# Driver.net
KiCad netlist of a schematic drawn in Altium Designer
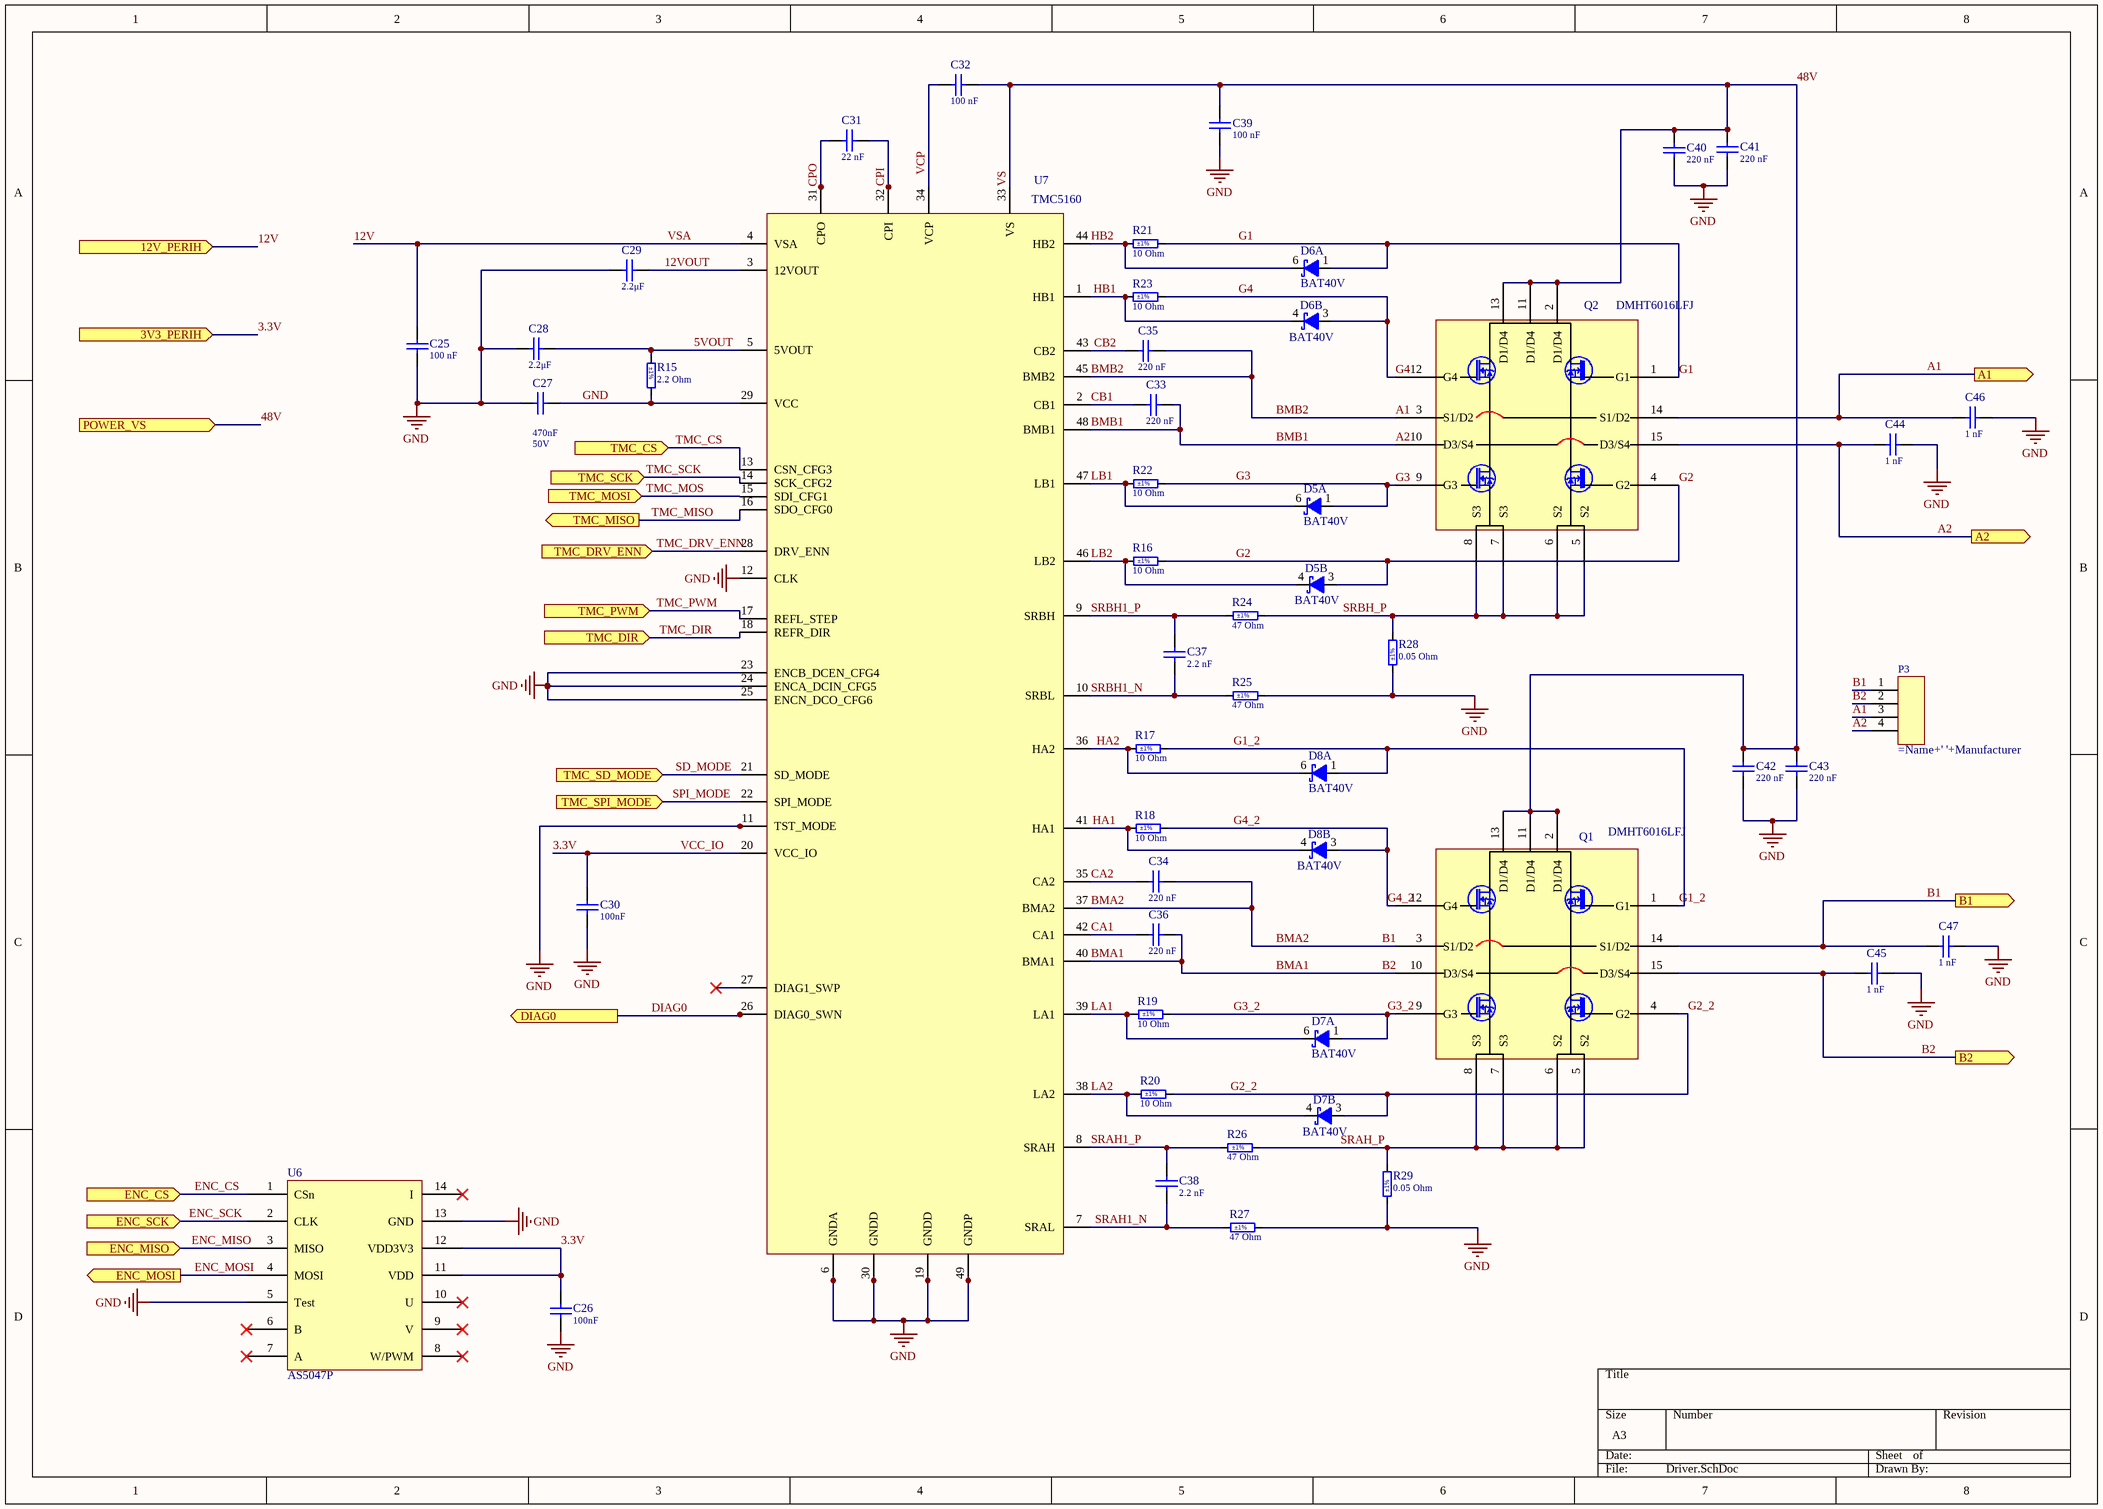
[diagram p0: Driver.SchDoc]

(export (version "E")
  (design (tool "Eeschema 10.0.6"))
  (components
    (comp (ref "C25")
      (value "100 nF 100V X5R ±10%")
      (footprint "capasitors:0402")
      (description "Ceramic capacitor")
      (fields
        (field (name "VOLTAGE") "100V")
        (field (name "TOLERANCE") "±10%")
        (field (name "CAPACITANCE") "100 nF")
      )
      (libsource (lib "passive") (part "Capacitor ceramic"))
    )
    (comp (ref "C26")
      (value "100nF 16V X7R ±10%")
      (footprint "capasitors:0402")
      (description "Ceramic capacitor")
      (fields
        (field (name "VOLTAGE") "16V")
        (field (name "TOLERANCE") "±10%")
        (field (name "CAPACITANCE") "100nF")
      )
      (libsource (lib "passive") (part "Capacitor ceramic"))
    )
    (comp (ref "C27")
      (value "470nF 50V ±10%")
      (footprint "0402")
      (description "Capacitor")
      (fields
        (field (name "TOLERANCE") "±10%")
        (field (name "CAPACITANCE") "470nF")
        (field (name "VOLTAGE") "50V")
        (field (name "MANUFACTURER") "Walsin")
      )
      (libsource (lib "Integrated_Library_Rassipuha_ZEN") (part "Cap"))
    )
    (comp (ref "C28")
      (value "2.2μF 16V X5R 20%")
      (footprint "capasitors:0402")
      (description "Ceramic capacitor")
      (fields
        (field (name "VOLTAGE") "16V")
        (field (name "TOLERANCE") "20%")
        (field (name "CAPACITANCE") "2.2μF")
      )
      (libsource (lib "passive") (part "Capacitor ceramic"))
    )
    (comp (ref "C29")
      (value "2.2μF 16V X5R 20%")
      (footprint "capasitors:0402")
      (description "Ceramic capacitor")
      (fields
        (field (name "VOLTAGE") "16V")
        (field (name "TOLERANCE") "20%")
        (field (name "CAPACITANCE") "2.2μF")
      )
      (libsource (lib "passive") (part "Capacitor ceramic"))
    )
    (comp (ref "C30")
      (value "100nF 16V X7R ±10%")
      (footprint "capasitors:0402")
      (description "Ceramic capacitor")
      (fields
        (field (name "VOLTAGE") "16V")
        (field (name "TOLERANCE") "±10%")
        (field (name "CAPACITANCE") "100nF")
      )
      (libsource (lib "passive") (part "Capacitor ceramic"))
    )
    (comp (ref "C31")
      (value "22 nF 100V X7R ±10%")
      (footprint "capasitors:0603")
      (description "Ceramic capacitor")
      (fields
        (field (name "VOLTAGE") "100V")
        (field (name "TOLERANCE") "±10%")
        (field (name "CAPACITANCE") "22 nF")
      )
      (libsource (lib "passive") (part "Capacitor ceramic"))
    )
    (comp (ref "C32")
      (value "100 nF 100V X5R ±10%")
      (footprint "capasitors:0402")
      (description "Ceramic capacitor")
      (fields
        (field (name "VOLTAGE") "100V")
        (field (name "TOLERANCE") "±10%")
        (field (name "CAPACITANCE") "100 nF")
      )
      (libsource (lib "passive") (part "Capacitor ceramic"))
    )
    (comp (ref "C33")
      (value "220 nF 25 X7R ±10%")
      (footprint "capasitors:0402")
      (description "Ceramic capacitor")
      (fields
        (field (name "VOLTAGE") "25")
        (field (name "TOLERANCE") "±10%")
        (field (name "CAPACITANCE") "220 nF")
      )
      (libsource (lib "passive") (part "Capacitor ceramic"))
    )
    (comp (ref "C34")
      (value "220 nF 25 X7R ±10%")
      (footprint "capasitors:0402")
      (description "Ceramic capacitor")
      (fields
        (field (name "VOLTAGE") "25")
        (field (name "TOLERANCE") "±10%")
        (field (name "CAPACITANCE") "220 nF")
      )
      (libsource (lib "passive") (part "Capacitor ceramic"))
    )
    (comp (ref "C35")
      (value "220 nF 25 X7R ±10%")
      (footprint "capasitors:0603")
      (description "Ceramic capacitor")
      (fields
        (field (name "VOLTAGE") "25")
        (field (name "TOLERANCE") "±10%")
        (field (name "CAPACITANCE") "220 nF")
      )
      (libsource (lib "passive") (part "Capacitor ceramic"))
    )
    (comp (ref "C36")
      (value "220 nF 25 X7R ±10%")
      (footprint "capasitors:0603")
      (description "Ceramic capacitor")
      (fields
        (field (name "VOLTAGE") "25")
        (field (name "TOLERANCE") "±10%")
        (field (name "CAPACITANCE") "220 nF")
      )
      (libsource (lib "passive") (part "Capacitor ceramic"))
    )
    (comp (ref "C37")
      (value "2.2 nF 100V X7R ±10%")
      (footprint "capasitors:0402")
      (description "Ceramic capacitor")
      (fields
        (field (name "VOLTAGE") "100V")
        (field (name "TOLERANCE") "±10%")
        (field (name "CAPACITANCE") "2.2 nF")
      )
      (libsource (lib "passive") (part "Capacitor ceramic"))
    )
    (comp (ref "C38")
      (value "2.2 nF 100V X7R ±10%")
      (footprint "capasitors:0402")
      (description "Ceramic capacitor")
      (fields
        (field (name "VOLTAGE") "100V")
        (field (name "TOLERANCE") "±10%")
        (field (name "CAPACITANCE") "2.2 nF")
      )
      (libsource (lib "passive") (part "Capacitor ceramic"))
    )
    (comp (ref "C39")
      (value "100 nF 100V X5R ±10%")
      (footprint "capasitors:0402")
      (description "Ceramic capacitor")
      (fields
        (field (name "VOLTAGE") "100V")
        (field (name "TOLERANCE") "±10%")
        (field (name "CAPACITANCE") "100 nF")
      )
      (libsource (lib "passive") (part "Capacitor ceramic"))
    )
    (comp (ref "C40")
      (value "220 nF 100V X7S ±10%")
      (footprint "capasitors:0603")
      (description "Ceramic capacitor")
      (fields
        (field (name "VOLTAGE") "100V")
        (field (name "TOLERANCE") "±10%")
        (field (name "CAPACITANCE") "220 nF")
      )
      (libsource (lib "passive") (part "Capacitor ceramic"))
    )
    (comp (ref "C41")
      (value "220 nF 100V X7S ±10%")
      (footprint "capasitors:0603")
      (description "Ceramic capacitor")
      (fields
        (field (name "VOLTAGE") "100V")
        (field (name "TOLERANCE") "±10%")
        (field (name "CAPACITANCE") "220 nF")
      )
      (libsource (lib "passive") (part "Capacitor ceramic"))
    )
    (comp (ref "C42")
      (value "220 nF 100V X7S ±10%")
      (footprint "capasitors:0603")
      (description "Ceramic capacitor")
      (fields
        (field (name "VOLTAGE") "100V")
        (field (name "TOLERANCE") "±10%")
        (field (name "CAPACITANCE") "220 nF")
      )
      (libsource (lib "passive") (part "Capacitor ceramic"))
    )
    (comp (ref "C43")
      (value "220 nF 100V X7S ±10%")
      (footprint "capasitors:0603")
      (description "Ceramic capacitor")
      (fields
        (field (name "VOLTAGE") "100V")
        (field (name "TOLERANCE") "±10%")
        (field (name "CAPACITANCE") "220 nF")
      )
      (libsource (lib "passive") (part "Capacitor ceramic"))
    )
    (comp (ref "C44")
      (value "1 nF 100V X7R ±10%")
      (footprint "capasitors:0402")
      (description "Ceramic capacitor")
      (fields
        (field (name "VOLTAGE") "100V")
        (field (name "TOLERANCE") "±10%")
        (field (name "CAPACITANCE") "1 nF")
      )
      (libsource (lib "passive") (part "Capacitor ceramic"))
    )
    (comp (ref "C45")
      (value "1 nF 100V X7R ±10%")
      (footprint "capasitors:0402")
      (description "Ceramic capacitor")
      (fields
        (field (name "VOLTAGE") "100V")
        (field (name "TOLERANCE") "±10%")
        (field (name "CAPACITANCE") "1 nF")
      )
      (libsource (lib "passive") (part "Capacitor ceramic"))
    )
    (comp (ref "C46")
      (value "1 nF 100V X7R ±10%")
      (footprint "capasitors:0402")
      (description "Ceramic capacitor")
      (fields
        (field (name "VOLTAGE") "100V")
        (field (name "TOLERANCE") "±10%")
        (field (name "CAPACITANCE") "1 nF")
      )
      (libsource (lib "passive") (part "Capacitor ceramic"))
    )
    (comp (ref "C47")
      (value "1 nF 100V X7R ±10%")
      (footprint "capasitors:0402")
      (description "Ceramic capacitor")
      (fields
        (field (name "VOLTAGE") "100V")
        (field (name "TOLERANCE") "±10%")
        (field (name "CAPACITANCE") "1 nF")
      )
      (libsource (lib "passive") (part "Capacitor ceramic"))
    )
    (comp (ref "D5") (value "BAT40V") (footprint "SOT563-6") (libsource (lib "") (part "BAT40V_1")))
    (comp (ref "D6") (value "BAT40V") (footprint "SOT563-6") (libsource (lib "") (part "BAT40V_1")))
    (comp (ref "D7")
      (value "BAT40V")
      (footprint "SOT563-6")
      (libsource (lib "Integrated_Library_Rassipuha_ZEN") (part "BAT40V"))
    )
    (comp (ref "D8")
      (value "BAT40V")
      (footprint "SOT563-6")
      (libsource (lib "Integrated_Library_Rassipuha_ZEN") (part "BAT40V"))
    )
    (comp (ref "P3")
      (value "Dinkle")
      (footprint "CONN_TERMBLOCK:15EDGRC-3.5-04P")
      (fields (field (name "MANUFACTURER") "Dinkle"))
      (libsource (lib "connector") (part "TerminalBlock4"))
    )
    (comp (ref "Q1")
      (value "DMHT6016LFJ")
      (footprint "V-DFN5045-12 (Type B)")
      (libsource (lib "Integrated_Library_Rassipuha_ZEN") (part "DMHT6016LFJ"))
    )
    (comp (ref "Q2")
      (value "DMHT6016LFJ")
      (footprint "V-DFN5045-12 (Type B)")
      (libsource (lib "Integrated_Library_Rassipuha_ZEN") (part "DMHT6016LFJ"))
    )
    (comp (ref "R15")
      (value "2.2 Ohm 1/10 W")
      (footprint "resistor:0603")
      (description "Thik Film Chip Resistor")
      (fields
        (field (name "POWER") "1/10 W")
        (field (name "TOLERANCE") "±1%")
        (field (name "RESISTANCE") "2.2 Ohm")
      )
      (libsource (lib "passive") (part "Resistor"))
    )
    (comp (ref "R16")
      (value "10 Ohm 1/16 W")
      (footprint "resistor:0402")
      (description "Thik Film Chip Resistor")
      (fields
        (field (name "POWER") "1/16 W")
        (field (name "TOLERANCE") "±1%")
        (field (name "RESISTANCE") "10 Ohm")
      )
      (libsource (lib "passive") (part "Resistor"))
    )
    (comp (ref "R17")
      (value "10 Ohm 1/16 W")
      (footprint "resistor:0402")
      (description "Thik Film Chip Resistor")
      (fields
        (field (name "POWER") "1/16 W")
        (field (name "TOLERANCE") "±1%")
        (field (name "RESISTANCE") "10 Ohm")
      )
      (libsource (lib "passive") (part "Resistor"))
    )
    (comp (ref "R18")
      (value "10 Ohm 1/16 W")
      (footprint "resistor:0402")
      (description "Thik Film Chip Resistor")
      (fields
        (field (name "POWER") "1/16 W")
        (field (name "TOLERANCE") "±1%")
        (field (name "RESISTANCE") "10 Ohm")
      )
      (libsource (lib "passive") (part "Resistor"))
    )
    (comp (ref "R19")
      (value "10 Ohm 1/16 W")
      (footprint "resistor:0402")
      (description "Thik Film Chip Resistor")
      (fields
        (field (name "POWER") "1/16 W")
        (field (name "TOLERANCE") "±1%")
        (field (name "RESISTANCE") "10 Ohm")
      )
      (libsource (lib "passive") (part "Resistor"))
    )
    (comp (ref "R20")
      (value "10 Ohm 1/16 W")
      (footprint "resistor:0402")
      (description "Thik Film Chip Resistor")
      (fields
        (field (name "POWER") "1/16 W")
        (field (name "TOLERANCE") "±1%")
        (field (name "RESISTANCE") "10 Ohm")
      )
      (libsource (lib "passive") (part "Resistor"))
    )
    (comp (ref "R21")
      (value "10 Ohm 1/16 W")
      (footprint "resistor:0402")
      (description "Thik Film Chip Resistor")
      (fields
        (field (name "POWER") "1/16 W")
        (field (name "TOLERANCE") "±1%")
        (field (name "RESISTANCE") "10 Ohm")
      )
      (libsource (lib "passive") (part "Resistor"))
    )
    (comp (ref "R22")
      (value "10 Ohm 1/16 W")
      (footprint "resistor:0402")
      (description "Thik Film Chip Resistor")
      (fields
        (field (name "POWER") "1/16 W")
        (field (name "TOLERANCE") "±1%")
        (field (name "RESISTANCE") "10 Ohm")
      )
      (libsource (lib "passive") (part "Resistor"))
    )
    (comp (ref "R23")
      (value "10 Ohm 1/16 W")
      (footprint "resistor:0402")
      (description "Thik Film Chip Resistor")
      (fields
        (field (name "POWER") "1/16 W")
        (field (name "TOLERANCE") "±1%")
        (field (name "RESISTANCE") "10 Ohm")
      )
      (libsource (lib "passive") (part "Resistor"))
    )
    (comp (ref "R24")
      (value "47 Ohm 1/16 W")
      (footprint "resistor:0402")
      (description "Thik Film Chip Resistor")
      (fields
        (field (name "POWER") "1/16 W")
        (field (name "TOLERANCE") "±1%")
        (field (name "RESISTANCE") "47 Ohm")
      )
      (libsource (lib "passive") (part "Resistor"))
    )
    (comp (ref "R25")
      (value "47 Ohm 1/16 W")
      (footprint "resistor:0402")
      (description "Thik Film Chip Resistor")
      (fields
        (field (name "POWER") "1/16 W")
        (field (name "TOLERANCE") "±1%")
        (field (name "RESISTANCE") "47 Ohm")
      )
      (libsource (lib "passive") (part "Resistor"))
    )
    (comp (ref "R26")
      (value "47 Ohm 1/16 W")
      (footprint "resistor:0402")
      (description "Thik Film Chip Resistor")
      (fields
        (field (name "POWER") "1/16 W")
        (field (name "TOLERANCE") "±1%")
        (field (name "RESISTANCE") "47 Ohm")
      )
      (libsource (lib "passive") (part "Resistor"))
    )
    (comp (ref "R27")
      (value "47 Ohm 1/16 W")
      (footprint "resistor:0402")
      (description "Thik Film Chip Resistor")
      (fields
        (field (name "POWER") "1/16 W")
        (field (name "TOLERANCE") "±1%")
        (field (name "RESISTANCE") "47 Ohm")
      )
      (libsource (lib "passive") (part "Resistor"))
    )
    (comp (ref "R28")
      (value "0.05 Ohm 1 W")
      (footprint "resistor:1206")
      (description "Thik Film Chip Resistor")
      (fields
        (field (name "POWER") "1 W")
        (field (name "TOLERANCE") "±1%")
        (field (name "RESISTANCE") "0.05 Ohm")
      )
      (libsource (lib "passive") (part "Resistor"))
    )
    (comp (ref "R29")
      (value "0.05 Ohm 1 W")
      (footprint "resistor:1206")
      (description "Thik Film Chip Resistor")
      (fields
        (field (name "POWER") "1 W")
        (field (name "TOLERANCE") "±1%")
        (field (name "RESISTANCE") "0.05 Ohm")
      )
      (libsource (lib "passive") (part "Resistor"))
    )
    (comp (ref "U6")
      (value "AS5047P")
      (footprint "TSSOP-14-0.65")
      (libsource (lib "Integrated_Library_IC_ZEN") (part "AS5047P"))
    )
    (comp (ref "U7")
      (value "TMC5160")
      (footprint "TQFP48-0.5-EP")
      (libsource (lib "ic_driver") (part "TMC5160"))
    )
  )
  (nets
    (net (code "1") (name "/3.3V") (class "Default")
      (node (ref "C26") (pin "2") (pinfunction "2_2") (pintype "passive"))
      (node (ref "C30") (pin "2") (pinfunction "2_2") (pintype "passive"))
      (node (ref "U6") (pin "11") (pinfunction "VDD_11") (pintype "passive"))
      (node (ref "U6") (pin "12") (pinfunction "VDD3V3_12") (pintype "passive"))
      (node (ref "U7") (pin "20") (pinfunction "VCC_IO_20") (pintype "passive"))
    )
    (net (code "2") (name "/5VOUT") (class "Default")
      (node (ref "C28") (pin "2") (pinfunction "2_2") (pintype "passive"))
      (node (ref "R15") (pin "1") (pinfunction "1_1") (pintype "passive"))
      (node (ref "U7") (pin "5") (pinfunction "5VOUT_5") (pintype "passive"))
    )
    (net (code "3") (name "/12V") (class "Default")
      (node (ref "C25") (pin "1") (pinfunction "1_1") (pintype "passive"))
      (node (ref "U7") (pin "4") (pinfunction "VSA_4") (pintype "passive"))
    )
    (net (code "4") (name "/12VOUT") (class "Default")
      (node (ref "C29") (pin "2") (pinfunction "2_2") (pintype "passive"))
      (node (ref "U7") (pin "3") (pinfunction "12VOUT_3") (pintype "passive"))
    )
    (net (code "5") (name "/48V") (class "Default")
      (node (ref "C32") (pin "2") (pinfunction "2_2") (pintype "passive"))
      (node (ref "C39") (pin "1") (pinfunction "1_1") (pintype "passive"))
      (node (ref "C40") (pin "1") (pinfunction "1_1") (pintype "passive"))
      (node (ref "C41") (pin "2") (pinfunction "2_2") (pintype "passive"))
      (node (ref "C42") (pin "2") (pinfunction "2_2") (pintype "passive"))
      (node (ref "C43") (pin "2") (pinfunction "2_2") (pintype "passive"))
      (node (ref "Q1") (pin "11") (pinfunction "D1/D4_11") (pintype "passive"))
      (node (ref "Q1") (pin "13") (pinfunction "D1/D4_13") (pintype "passive"))
      (node (ref "Q1") (pin "2") (pinfunction "D1/D4_2") (pintype "passive"))
      (node (ref "Q2") (pin "11") (pinfunction "D1/D4_11") (pintype "passive"))
      (node (ref "Q2") (pin "13") (pinfunction "D1/D4_13") (pintype "passive"))
      (node (ref "Q2") (pin "2") (pinfunction "D1/D4_2") (pintype "passive"))
      (node (ref "U7") (pin "33") (pinfunction "VS_33") (pintype "passive"))
    )
    (net (code "6") (name "/A1") (class "Default")
      (node (ref "C35") (pin "2") (pinfunction "2_2") (pintype "passive"))
      (node (ref "C46") (pin "2") (pinfunction "2_2") (pintype "passive"))
      (node (ref "P3") (pin "3") (pinfunction "3_3") (pintype "passive"))
      (node (ref "Q2") (pin "14") (pinfunction "S1/D2_14") (pintype "passive"))
      (node (ref "Q2") (pin "3") (pinfunction "S1/D2_3") (pintype "passive"))
      (node (ref "U7") (pin "45") (pinfunction "BMB2_45") (pintype "passive"))
    )
    (net (code "7") (name "/A2") (class "Default")
      (node (ref "C33") (pin "2") (pinfunction "2_2") (pintype "passive"))
      (node (ref "C44") (pin "2") (pinfunction "2_2") (pintype "passive"))
      (node (ref "P3") (pin "4") (pinfunction "4_4") (pintype "passive"))
      (node (ref "Q2") (pin "10") (pinfunction "D3/S4_10") (pintype "passive"))
      (node (ref "Q2") (pin "15") (pinfunction "D3/S4_15") (pintype "passive"))
      (node (ref "U7") (pin "48") (pinfunction "BMB1_48") (pintype "passive"))
    )
    (net (code "8") (name "/B1") (class "Default")
      (node (ref "C34") (pin "2") (pinfunction "2_2") (pintype "passive"))
      (node (ref "C47") (pin "2") (pinfunction "2_2") (pintype "passive"))
      (node (ref "P3") (pin "1") (pinfunction "1_1") (pintype "passive"))
      (node (ref "Q1") (pin "14") (pinfunction "S1/D2_14") (pintype "passive"))
      (node (ref "Q1") (pin "3") (pinfunction "S1/D2_3") (pintype "passive"))
      (node (ref "U7") (pin "37") (pinfunction "BMA2_37") (pintype "passive"))
    )
    (net (code "9") (name "/B2") (class "Default")
      (node (ref "C36") (pin "2") (pinfunction "2_2") (pintype "passive"))
      (node (ref "C45") (pin "2") (pinfunction "2_2") (pintype "passive"))
      (node (ref "P3") (pin "2") (pinfunction "2_2") (pintype "passive"))
      (node (ref "Q1") (pin "10") (pinfunction "D3/S4_10") (pintype "passive"))
      (node (ref "Q1") (pin "15") (pinfunction "D3/S4_15") (pintype "passive"))
      (node (ref "U7") (pin "40") (pinfunction "BMA1_40") (pintype "passive"))
    )
    (net (code "10") (name "/CA1") (class "Default")
      (node (ref "C36") (pin "1") (pinfunction "1_1") (pintype "passive"))
      (node (ref "U7") (pin "42") (pinfunction "CA1_42") (pintype "passive"))
    )
    (net (code "11") (name "/CA2") (class "Default")
      (node (ref "C34") (pin "1") (pinfunction "1_1") (pintype "passive"))
      (node (ref "U7") (pin "35") (pinfunction "CA2_35") (pintype "passive"))
    )
    (net (code "12") (name "/CB1") (class "Default")
      (node (ref "C33") (pin "1") (pinfunction "1_1") (pintype "passive"))
      (node (ref "U7") (pin "2") (pinfunction "CB1_2") (pintype "passive"))
    )
    (net (code "13") (name "/CB2") (class "Default")
      (node (ref "C35") (pin "1") (pinfunction "1_1") (pintype "passive"))
      (node (ref "U7") (pin "43") (pinfunction "CB2_43") (pintype "passive"))
    )
    (net (code "14") (name "/CPI") (class "Default")
      (node (ref "C31") (pin "2") (pinfunction "2_2") (pintype "passive"))
      (node (ref "U7") (pin "32") (pinfunction "CPI_32") (pintype "passive"))
    )
    (net (code "15") (name "/CPO") (class "Default")
      (node (ref "C31") (pin "1") (pinfunction "1_1") (pintype "passive"))
      (node (ref "U7") (pin "31") (pinfunction "CPO_31") (pintype "passive"))
    )
    (net (code "16") (name "/DIAG0") (class "Default")
      (node (ref "U7") (pin "26") (pinfunction "DIAG0_SWN_26") (pintype "passive"))
    )
    (net (code "17") (name "/ENC_CS") (class "Default")
      (node (ref "U6") (pin "1") (pinfunction "CSn_1") (pintype "passive"))
    )
    (net (code "18") (name "/ENC_MISO") (class "Default")
      (node (ref "U6") (pin "3") (pinfunction "MISO_3") (pintype "passive"))
    )
    (net (code "19") (name "/ENC_MOSI") (class "Default")
      (node (ref "U6") (pin "4") (pinfunction "MOSI_4") (pintype "passive"))
    )
    (net (code "20") (name "/ENC_SCK") (class "Default")
      (node (ref "U6") (pin "2") (pinfunction "CLK_2") (pintype "passive"))
    )
    (net (code "21") (name "/G1") (class "Default")
      (node (ref "D6") (pin "1") (pinfunction "1_1") (pintype "passive"))
      (node (ref "Q2") (pin "1") (pinfunction "G1_1") (pintype "passive"))
      (node (ref "R21") (pin "2") (pinfunction "2_2") (pintype "passive"))
    )
    (net (code "22") (name "/G1_2") (class "Default")
      (node (ref "D8") (pin "1") (pinfunction "1_1") (pintype "passive"))
      (node (ref "Q1") (pin "1") (pinfunction "G1_1") (pintype "passive"))
      (node (ref "R17") (pin "2") (pinfunction "2_2") (pintype "passive"))
    )
    (net (code "23") (name "/G2") (class "Default")
      (node (ref "D5") (pin "3") (pinfunction "1_3") (pintype "passive"))
      (node (ref "Q2") (pin "4") (pinfunction "G2_4") (pintype "passive"))
      (node (ref "R16") (pin "2") (pinfunction "2_2") (pintype "passive"))
    )
    (net (code "24") (name "/G2_2") (class "Default")
      (node (ref "D7") (pin "3") (pinfunction "1_3") (pintype "passive"))
      (node (ref "Q1") (pin "4") (pinfunction "G2_4") (pintype "passive"))
      (node (ref "R20") (pin "2") (pinfunction "2_2") (pintype "passive"))
    )
    (net (code "25") (name "/G3") (class "Default")
      (node (ref "D5") (pin "1") (pinfunction "1_1") (pintype "passive"))
      (node (ref "Q2") (pin "9") (pinfunction "G3_9") (pintype "passive"))
      (node (ref "R22") (pin "2") (pinfunction "2_2") (pintype "passive"))
    )
    (net (code "26") (name "/G3_2") (class "Default")
      (node (ref "D7") (pin "1") (pinfunction "1_1") (pintype "passive"))
      (node (ref "Q1") (pin "9") (pinfunction "G3_9") (pintype "passive"))
      (node (ref "R19") (pin "2") (pinfunction "2_2") (pintype "passive"))
    )
    (net (code "27") (name "/G4") (class "Default")
      (node (ref "D6") (pin "3") (pinfunction "1_3") (pintype "passive"))
      (node (ref "Q2") (pin "12") (pinfunction "G4_12") (pintype "passive"))
      (node (ref "R23") (pin "2") (pinfunction "2_2") (pintype "passive"))
    )
    (net (code "28") (name "/G4_2") (class "Default")
      (node (ref "D8") (pin "3") (pinfunction "1_3") (pintype "passive"))
      (node (ref "Q1") (pin "12") (pinfunction "G4_12") (pintype "passive"))
      (node (ref "R18") (pin "2") (pinfunction "2_2") (pintype "passive"))
    )
    (net (code "29") (name "/HA1") (class "Default")
      (node (ref "D8") (pin "4") (pinfunction "2_4") (pintype "passive"))
      (node (ref "R18") (pin "1") (pinfunction "1_1") (pintype "passive"))
      (node (ref "U7") (pin "41") (pinfunction "HA1_41") (pintype "passive"))
    )
    (net (code "30") (name "/HA2") (class "Default")
      (node (ref "D8") (pin "6") (pinfunction "2_6") (pintype "passive"))
      (node (ref "R17") (pin "1") (pinfunction "1_1") (pintype "passive"))
      (node (ref "U7") (pin "36") (pinfunction "HA2_36") (pintype "passive"))
    )
    (net (code "31") (name "/HB1") (class "Default")
      (node (ref "D6") (pin "4") (pinfunction "2_4") (pintype "passive"))
      (node (ref "R23") (pin "1") (pinfunction "1_1") (pintype "passive"))
      (node (ref "U7") (pin "1") (pinfunction "HB1_1") (pintype "passive"))
    )
    (net (code "32") (name "/HB2") (class "Default")
      (node (ref "D6") (pin "6") (pinfunction "2_6") (pintype "passive"))
      (node (ref "R21") (pin "1") (pinfunction "1_1") (pintype "passive"))
      (node (ref "U7") (pin "44") (pinfunction "HB2_44") (pintype "passive"))
    )
    (net (code "33") (name "/LA1") (class "Default")
      (node (ref "D7") (pin "6") (pinfunction "2_6") (pintype "passive"))
      (node (ref "R19") (pin "1") (pinfunction "1_1") (pintype "passive"))
      (node (ref "U7") (pin "39") (pinfunction "LA1_39") (pintype "passive"))
    )
    (net (code "34") (name "/LA2") (class "Default")
      (node (ref "D7") (pin "4") (pinfunction "2_4") (pintype "passive"))
      (node (ref "R20") (pin "1") (pinfunction "1_1") (pintype "passive"))
      (node (ref "U7") (pin "38") (pinfunction "LA2_38") (pintype "passive"))
    )
    (net (code "35") (name "/LB1") (class "Default")
      (node (ref "D5") (pin "6") (pinfunction "2_6") (pintype "passive"))
      (node (ref "R22") (pin "1") (pinfunction "1_1") (pintype "passive"))
      (node (ref "U7") (pin "47") (pinfunction "LB1_47") (pintype "passive"))
    )
    (net (code "36") (name "/LB2") (class "Default")
      (node (ref "D5") (pin "4") (pinfunction "2_4") (pintype "passive"))
      (node (ref "R16") (pin "1") (pinfunction "1_1") (pintype "passive"))
      (node (ref "U7") (pin "46") (pinfunction "LB2_46") (pintype "passive"))
    )
    (net (code "37") (name "/SD_MODE") (class "Default")
      (node (ref "U7") (pin "21") (pinfunction "SD_MODE_21") (pintype "passive"))
    )
    (net (code "38") (name "/SPI_MODE") (class "Default")
      (node (ref "U7") (pin "22") (pinfunction "SPI_MODE_22") (pintype "passive"))
    )
    (net (code "39") (name "/SRAH1_N") (class "Default")
      (node (ref "C38") (pin "1") (pinfunction "1_1") (pintype "passive"))
      (node (ref "R27") (pin "1") (pinfunction "1_1") (pintype "passive"))
      (node (ref "U7") (pin "7") (pinfunction "SRAL_7") (pintype "passive"))
    )
    (net (code "40") (name "/SRAH1_P") (class "Default")
      (node (ref "C38") (pin "2") (pinfunction "2_2") (pintype "passive"))
      (node (ref "R26") (pin "1") (pinfunction "1_1") (pintype "passive"))
      (node (ref "U7") (pin "8") (pinfunction "SRAH_8") (pintype "passive"))
    )
    (net (code "41") (name "/SRAH_P") (class "Default")
      (node (ref "Q1") (pin "5") (pinfunction "S2_5") (pintype "passive"))
      (node (ref "Q1") (pin "6") (pinfunction "S2_6") (pintype "passive"))
      (node (ref "Q1") (pin "7") (pinfunction "S3_7") (pintype "passive"))
      (node (ref "Q1") (pin "8") (pinfunction "S3_8") (pintype "passive"))
      (node (ref "R26") (pin "2") (pinfunction "2_2") (pintype "passive"))
      (node (ref "R29") (pin "2") (pinfunction "2_2") (pintype "passive"))
    )
    (net (code "42") (name "/SRBH1_N") (class "Default")
      (node (ref "C37") (pin "1") (pinfunction "1_1") (pintype "passive"))
      (node (ref "R25") (pin "1") (pinfunction "1_1") (pintype "passive"))
      (node (ref "U7") (pin "10") (pinfunction "SRBL_10") (pintype "passive"))
    )
    (net (code "43") (name "/SRBH1_P") (class "Default")
      (node (ref "C37") (pin "2") (pinfunction "2_2") (pintype "passive"))
      (node (ref "R24") (pin "1") (pinfunction "1_1") (pintype "passive"))
      (node (ref "U7") (pin "9") (pinfunction "SRBH_9") (pintype "passive"))
    )
    (net (code "44") (name "/SRBH_P") (class "Default")
      (node (ref "Q2") (pin "5") (pinfunction "S2_5") (pintype "passive"))
      (node (ref "Q2") (pin "6") (pinfunction "S2_6") (pintype "passive"))
      (node (ref "Q2") (pin "7") (pinfunction "S3_7") (pintype "passive"))
      (node (ref "Q2") (pin "8") (pinfunction "S3_8") (pintype "passive"))
      (node (ref "R24") (pin "2") (pinfunction "2_2") (pintype "passive"))
      (node (ref "R28") (pin "2") (pinfunction "2_2") (pintype "passive"))
    )
    (net (code "45") (name "/TMC_CS") (class "Default")
      (node (ref "U7") (pin "13") (pinfunction "CSN_CFG3_13") (pintype "passive"))
    )
    (net (code "46") (name "/TMC_DIR") (class "Default")
      (node (ref "U7") (pin "18") (pinfunction "REFR_DIR_18") (pintype "passive"))
    )
    (net (code "47") (name "/TMC_DRV_ENN") (class "Default")
      (node (ref "U7") (pin "28") (pinfunction "DRV_ENN_28") (pintype "passive"))
    )
    (net (code "48") (name "/TMC_MISO") (class "Default")
      (node (ref "U7") (pin "16") (pinfunction "SDO_CFG0_16") (pintype "passive"))
    )
    (net (code "49") (name "/TMC_MOS") (class "Default")
      (node (ref "U7") (pin "15") (pinfunction "SDI_CFG1_15") (pintype "passive"))
    )
    (net (code "50") (name "/TMC_PWM") (class "Default")
      (node (ref "U7") (pin "17") (pinfunction "REFL_STEP_17") (pintype "passive"))
    )
    (net (code "51") (name "/TMC_SCK") (class "Default")
      (node (ref "U7") (pin "14") (pinfunction "SCK_CFG2_14") (pintype "passive"))
    )
    (net (code "52") (name "/VCP") (class "Default")
      (node (ref "C32") (pin "1") (pinfunction "1_1") (pintype "passive"))
      (node (ref "U7") (pin "34") (pinfunction "VCP_34") (pintype "passive"))
    )
    (net (code "53") (name "GND") (class "Default")
      (node (ref "C25") (pin "2") (pinfunction "2_2") (pintype "passive"))
      (node (ref "C26") (pin "1") (pinfunction "1_1") (pintype "passive"))
      (node (ref "C27") (pin "1") (pinfunction "1_1") (pintype "passive"))
      (node (ref "C27") (pin "2") (pinfunction "2_2") (pintype "passive"))
      (node (ref "C28") (pin "1") (pinfunction "1_1") (pintype "passive"))
      (node (ref "C29") (pin "1") (pinfunction "1_1") (pintype "passive"))
      (node (ref "C30") (pin "1") (pinfunction "1_1") (pintype "passive"))
      (node (ref "C39") (pin "2") (pinfunction "2_2") (pintype "passive"))
      (node (ref "C40") (pin "2") (pinfunction "2_2") (pintype "passive"))
      (node (ref "C41") (pin "1") (pinfunction "1_1") (pintype "passive"))
      (node (ref "C42") (pin "1") (pinfunction "1_1") (pintype "passive"))
      (node (ref "C43") (pin "1") (pinfunction "1_1") (pintype "passive"))
      (node (ref "C44") (pin "1") (pinfunction "1_1") (pintype "passive"))
      (node (ref "C45") (pin "1") (pinfunction "1_1") (pintype "passive"))
      (node (ref "C46") (pin "1") (pinfunction "1_1") (pintype "passive"))
      (node (ref "C47") (pin "1") (pinfunction "1_1") (pintype "passive"))
      (node (ref "R15") (pin "2") (pinfunction "2_2") (pintype "passive"))
      (node (ref "R25") (pin "2") (pinfunction "2_2") (pintype "passive"))
      (node (ref "R27") (pin "2") (pinfunction "2_2") (pintype "passive"))
      (node (ref "R28") (pin "1") (pinfunction "1_1") (pintype "passive"))
      (node (ref "R29") (pin "1") (pinfunction "1_1") (pintype "passive"))
      (node (ref "U6") (pin "13") (pinfunction "GND_13") (pintype "passive"))
      (node (ref "U6") (pin "5") (pinfunction "Test_5") (pintype "passive"))
      (node (ref "U7") (pin "11") (pinfunction "TST_MODE_11") (pintype "passive"))
      (node (ref "U7") (pin "12") (pinfunction "CLK_12") (pintype "passive"))
      (node (ref "U7") (pin "19") (pinfunction "GNDD_19") (pintype "passive"))
      (node (ref "U7") (pin "23") (pinfunction "ENCB_DCEN_CFG4_23") (pintype "passive"))
      (node (ref "U7") (pin "24") (pinfunction "ENCA_DCIN_CFG5_24") (pintype "passive"))
      (node (ref "U7") (pin "25") (pinfunction "ENCN_DCO_CFG6_25") (pintype "passive"))
      (node (ref "U7") (pin "29") (pinfunction "VCC_29") (pintype "passive"))
      (node (ref "U7") (pin "30") (pinfunction "GNDD_30") (pintype "passive"))
      (node (ref "U7") (pin "49") (pinfunction "GNDP_49") (pintype "passive"))
      (node (ref "U7") (pin "6") (pinfunction "GNDA_6") (pintype "passive"))
    )
    (net (code "54") (name "unconnected-(U6-A-Pad7)") (class "Default")
      (node (ref "U6") (pin "7") (pinfunction "A_7") (pintype "passive+no_connect"))
    )
    (net (code "55") (name "unconnected-(U6-B-Pad6)") (class "Default")
      (node (ref "U6") (pin "6") (pinfunction "B_6") (pintype "passive+no_connect"))
    )
    (net (code "56") (name "unconnected-(U6-I-Pad14)") (class "Default")
      (node (ref "U6") (pin "14") (pinfunction "I_14") (pintype "passive+no_connect"))
    )
    (net (code "57") (name "unconnected-(U6-U-Pad10)") (class "Default")
      (node (ref "U6") (pin "10") (pinfunction "U_10") (pintype "passive+no_connect"))
    )
    (net (code "58") (name "unconnected-(U6-V-Pad9)") (class "Default")
      (node (ref "U6") (pin "9") (pinfunction "V_9") (pintype "passive+no_connect"))
    )
    (net (code "59") (name "unconnected-(U6-W{slash}PWM-Pad8)") (class "Default")
      (node (ref "U6") (pin "8") (pinfunction "W/PWM_8") (pintype "passive+no_connect"))
    )
    (net (code "60") (name "unconnected-(U7-DIAG1_SWP-Pad27)") (class "Default")
      (node (ref "U7") (pin "27") (pinfunction "DIAG1_SWP_27") (pintype "passive+no_connect"))
    )
  )
)
